# LEDS.net
KiCad netlist of a schematic drawn in EAGLE
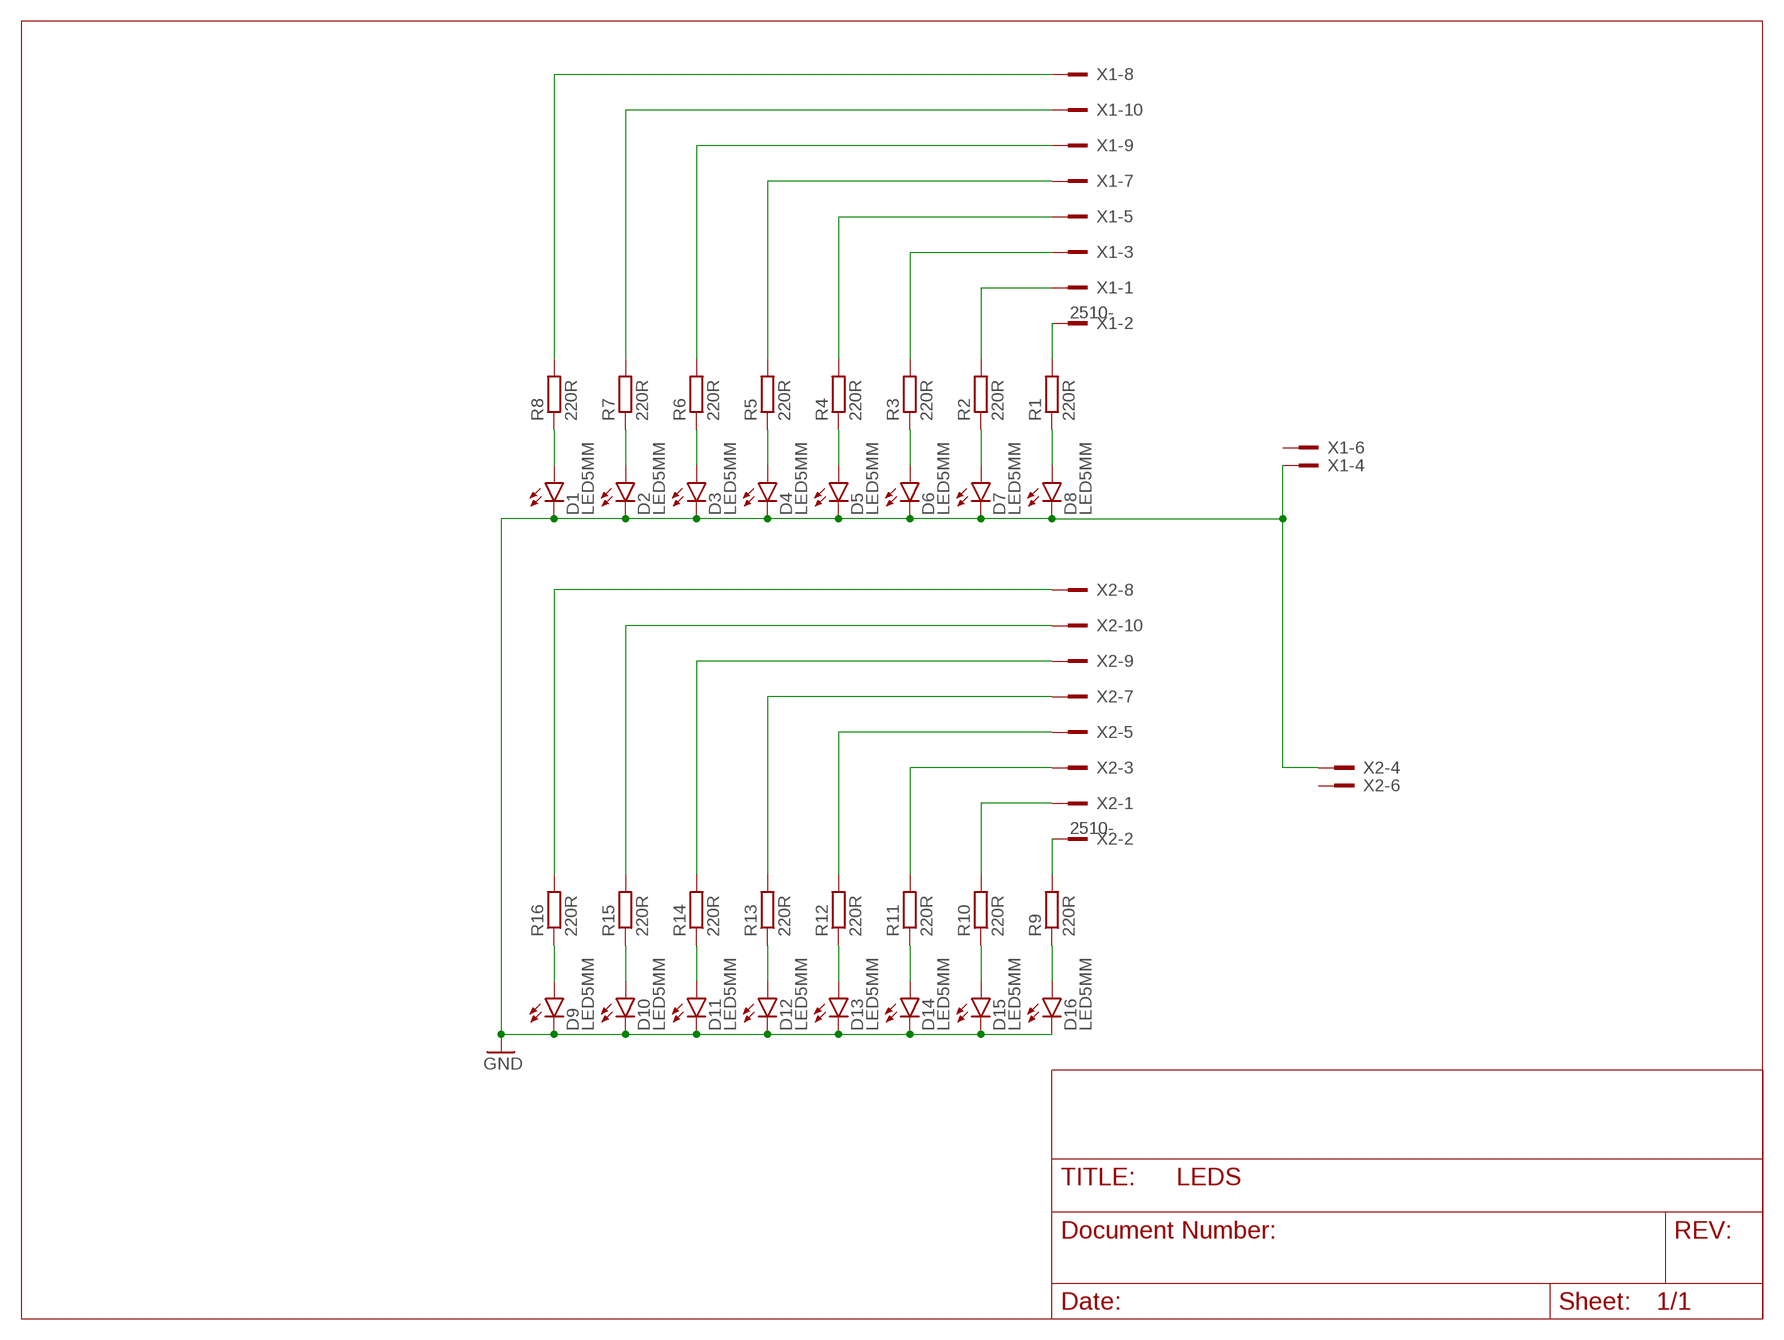
[diagram p0: schematic, sheet 1]

(export (version "E")
  (design (tool "Eeschema 10.0.6"))
  (components
    (comp (ref "D1")
      (value "LED5MM")
      (footprint "eagle-import:LED5MM")
      (libsource (lib "eagle-import") (part "LED5MM"))
    )
    (comp (ref "D2")
      (value "LED5MM")
      (footprint "eagle-import:LED5MM")
      (libsource (lib "eagle-import") (part "LED5MM"))
    )
    (comp (ref "D3")
      (value "LED5MM")
      (footprint "eagle-import:LED5MM")
      (libsource (lib "eagle-import") (part "LED5MM"))
    )
    (comp (ref "D4")
      (value "LED5MM")
      (footprint "eagle-import:LED5MM")
      (libsource (lib "eagle-import") (part "LED5MM"))
    )
    (comp (ref "D5")
      (value "LED5MM")
      (footprint "eagle-import:LED5MM")
      (libsource (lib "eagle-import") (part "LED5MM"))
    )
    (comp (ref "D6")
      (value "LED5MM")
      (footprint "eagle-import:LED5MM")
      (libsource (lib "eagle-import") (part "LED5MM"))
    )
    (comp (ref "D7")
      (value "LED5MM")
      (footprint "eagle-import:LED5MM")
      (libsource (lib "eagle-import") (part "LED5MM"))
    )
    (comp (ref "D8")
      (value "LED5MM")
      (footprint "eagle-import:LED5MM")
      (libsource (lib "eagle-import") (part "LED5MM"))
    )
    (comp (ref "D9")
      (value "LED5MM")
      (footprint "eagle-import:LED5MM")
      (libsource (lib "eagle-import") (part "LED5MM"))
    )
    (comp (ref "D10")
      (value "LED5MM")
      (footprint "eagle-import:LED5MM")
      (libsource (lib "eagle-import") (part "LED5MM"))
    )
    (comp (ref "D11")
      (value "LED5MM")
      (footprint "eagle-import:LED5MM")
      (libsource (lib "eagle-import") (part "LED5MM"))
    )
    (comp (ref "D12")
      (value "LED5MM")
      (footprint "eagle-import:LED5MM")
      (libsource (lib "eagle-import") (part "LED5MM"))
    )
    (comp (ref "D13")
      (value "LED5MM")
      (footprint "eagle-import:LED5MM")
      (libsource (lib "eagle-import") (part "LED5MM"))
    )
    (comp (ref "D14")
      (value "LED5MM")
      (footprint "eagle-import:LED5MM")
      (libsource (lib "eagle-import") (part "LED5MM"))
    )
    (comp (ref "D15")
      (value "LED5MM")
      (footprint "eagle-import:LED5MM")
      (libsource (lib "eagle-import") (part "LED5MM"))
    )
    (comp (ref "D16")
      (value "LED5MM")
      (footprint "eagle-import:LED5MM")
      (libsource (lib "eagle-import") (part "LED5MM"))
    )
    (comp (ref "R1")
      (value "220R")
      (footprint "eagle-import:0204_ELVYS")
      (libsource (lib "eagle-import") (part "R-EU_"))
    )
    (comp (ref "R2")
      (value "220R")
      (footprint "eagle-import:0204_ELVYS")
      (libsource (lib "eagle-import") (part "R-EU_"))
    )
    (comp (ref "R3")
      (value "220R")
      (footprint "eagle-import:0204_ELVYS")
      (libsource (lib "eagle-import") (part "R-EU_"))
    )
    (comp (ref "R4")
      (value "220R")
      (footprint "eagle-import:0204_ELVYS")
      (libsource (lib "eagle-import") (part "R-EU_"))
    )
    (comp (ref "R5")
      (value "220R")
      (footprint "eagle-import:0204_ELVYS")
      (libsource (lib "eagle-import") (part "R-EU_"))
    )
    (comp (ref "R6")
      (value "220R")
      (footprint "eagle-import:0204_ELVYS")
      (libsource (lib "eagle-import") (part "R-EU_"))
    )
    (comp (ref "R7")
      (value "220R")
      (footprint "eagle-import:0204_ELVYS")
      (libsource (lib "eagle-import") (part "R-EU_"))
    )
    (comp (ref "R8")
      (value "220R")
      (footprint "eagle-import:0204_ELVYS")
      (libsource (lib "eagle-import") (part "R-EU_"))
    )
    (comp (ref "R9")
      (value "220R")
      (footprint "eagle-import:0204_ELVYS")
      (libsource (lib "eagle-import") (part "R-EU_"))
    )
    (comp (ref "R10")
      (value "220R")
      (footprint "eagle-import:0204_ELVYS")
      (libsource (lib "eagle-import") (part "R-EU_"))
    )
    (comp (ref "R11")
      (value "220R")
      (footprint "eagle-import:0204_ELVYS")
      (libsource (lib "eagle-import") (part "R-EU_"))
    )
    (comp (ref "R12")
      (value "220R")
      (footprint "eagle-import:0204_ELVYS")
      (libsource (lib "eagle-import") (part "R-EU_"))
    )
    (comp (ref "R13")
      (value "220R")
      (footprint "eagle-import:0204_ELVYS")
      (libsource (lib "eagle-import") (part "R-EU_"))
    )
    (comp (ref "R14")
      (value "220R")
      (footprint "eagle-import:0204_ELVYS")
      (libsource (lib "eagle-import") (part "R-EU_"))
    )
    (comp (ref "R15")
      (value "220R")
      (footprint "eagle-import:0204_ELVYS")
      (libsource (lib "eagle-import") (part "R-EU_"))
    )
    (comp (ref "R16")
      (value "220R")
      (footprint "eagle-import:0204_ELVYS")
      (libsource (lib "eagle-import") (part "R-EU_"))
    )
    (comp (ref "X1")
      (value "2510-")
      (footprint "eagle-import:PAK100_2500-10")
      (fields (field (name "MF") "3M") (field (name "MPN") "2510-6002UB"))
      (libsource (lib "eagle-import") (part "2510-"))
    )
    (comp (ref "X2")
      (value "2510-")
      (footprint "eagle-import:PAK100_2500-10")
      (fields (field (name "MF") "3M") (field (name "MPN") "2510-6002UB"))
      (libsource (lib "eagle-import") (part "2510-"))
    )
  )
  (nets
    (net (code "1") (name "GND") (class "Default")
      (node (ref "D1") (pin "K") (pinfunction "C_K") (pintype "passive"))
      (node (ref "D10") (pin "K") (pinfunction "C_K") (pintype "passive"))
      (node (ref "D11") (pin "K") (pinfunction "C_K") (pintype "passive"))
      (node (ref "D12") (pin "K") (pinfunction "C_K") (pintype "passive"))
      (node (ref "D13") (pin "K") (pinfunction "C_K") (pintype "passive"))
      (node (ref "D14") (pin "K") (pinfunction "C_K") (pintype "passive"))
      (node (ref "D15") (pin "K") (pinfunction "C_K") (pintype "passive"))
      (node (ref "D16") (pin "K") (pinfunction "C_K") (pintype "passive"))
      (node (ref "D2") (pin "K") (pinfunction "C_K") (pintype "passive"))
      (node (ref "D3") (pin "K") (pinfunction "C_K") (pintype "passive"))
      (node (ref "D4") (pin "K") (pinfunction "C_K") (pintype "passive"))
      (node (ref "D5") (pin "K") (pinfunction "C_K") (pintype "passive"))
      (node (ref "D6") (pin "K") (pinfunction "C_K") (pintype "passive"))
      (node (ref "D7") (pin "K") (pinfunction "C_K") (pintype "passive"))
      (node (ref "D8") (pin "K") (pinfunction "C_K") (pintype "passive"))
      (node (ref "D9") (pin "K") (pinfunction "C_K") (pintype "passive"))
      (node (ref "X1") (pin "4") (pinfunction "KL_4") (pintype "passive"))
      (node (ref "X2") (pin "4") (pinfunction "KL_4") (pintype "passive"))
    )
    (net (code "2") (name "Net-(R1-1)") (class "Default")
      (node (ref "D8") (pin "A") (pinfunction "A_A") (pintype "passive"))
      (node (ref "R1") (pin "P$1") (pinfunction "1_P$1") (pintype "passive"))
    )
    (net (code "3") (name "Net-(R1-2)") (class "Default")
      (node (ref "R1") (pin "P$2") (pinfunction "2_P$2") (pintype "passive"))
      (node (ref "X1") (pin "2") (pinfunction "KL_2") (pintype "passive"))
    )
    (net (code "4") (name "Net-(R2-1)") (class "Default")
      (node (ref "D7") (pin "A") (pinfunction "A_A") (pintype "passive"))
      (node (ref "R2") (pin "P$1") (pinfunction "1_P$1") (pintype "passive"))
    )
    (net (code "5") (name "Net-(R2-2)") (class "Default")
      (node (ref "R2") (pin "P$2") (pinfunction "2_P$2") (pintype "passive"))
      (node (ref "X1") (pin "1") (pinfunction "KL_1") (pintype "passive"))
    )
    (net (code "6") (name "Net-(R3-1)") (class "Default")
      (node (ref "D6") (pin "A") (pinfunction "A_A") (pintype "passive"))
      (node (ref "R3") (pin "P$1") (pinfunction "1_P$1") (pintype "passive"))
    )
    (net (code "7") (name "Net-(R3-2)") (class "Default")
      (node (ref "R3") (pin "P$2") (pinfunction "2_P$2") (pintype "passive"))
      (node (ref "X1") (pin "3") (pinfunction "KL_3") (pintype "passive"))
    )
    (net (code "8") (name "Net-(R4-1)") (class "Default")
      (node (ref "D5") (pin "A") (pinfunction "A_A") (pintype "passive"))
      (node (ref "R4") (pin "P$1") (pinfunction "1_P$1") (pintype "passive"))
    )
    (net (code "9") (name "Net-(R4-2)") (class "Default")
      (node (ref "R4") (pin "P$2") (pinfunction "2_P$2") (pintype "passive"))
      (node (ref "X1") (pin "5") (pinfunction "KL_5") (pintype "passive"))
    )
    (net (code "10") (name "Net-(R5-1)") (class "Default")
      (node (ref "D4") (pin "A") (pinfunction "A_A") (pintype "passive"))
      (node (ref "R5") (pin "P$1") (pinfunction "1_P$1") (pintype "passive"))
    )
    (net (code "11") (name "Net-(R5-2)") (class "Default")
      (node (ref "R5") (pin "P$2") (pinfunction "2_P$2") (pintype "passive"))
      (node (ref "X1") (pin "7") (pinfunction "KL_7") (pintype "passive"))
    )
    (net (code "12") (name "Net-(R6-1)") (class "Default")
      (node (ref "D3") (pin "A") (pinfunction "A_A") (pintype "passive"))
      (node (ref "R6") (pin "P$1") (pinfunction "1_P$1") (pintype "passive"))
    )
    (net (code "13") (name "Net-(R6-2)") (class "Default")
      (node (ref "R6") (pin "P$2") (pinfunction "2_P$2") (pintype "passive"))
      (node (ref "X1") (pin "9") (pinfunction "KL_9") (pintype "passive"))
    )
    (net (code "14") (name "Net-(R7-1)") (class "Default")
      (node (ref "D2") (pin "A") (pinfunction "A_A") (pintype "passive"))
      (node (ref "R7") (pin "P$1") (pinfunction "1_P$1") (pintype "passive"))
    )
    (net (code "15") (name "Net-(R7-2)") (class "Default")
      (node (ref "R7") (pin "P$2") (pinfunction "2_P$2") (pintype "passive"))
      (node (ref "X1") (pin "10") (pinfunction "KL_10") (pintype "passive"))
    )
    (net (code "16") (name "Net-(R8-1)") (class "Default")
      (node (ref "D1") (pin "A") (pinfunction "A_A") (pintype "passive"))
      (node (ref "R8") (pin "P$1") (pinfunction "1_P$1") (pintype "passive"))
    )
    (net (code "17") (name "Net-(R8-2)") (class "Default")
      (node (ref "R8") (pin "P$2") (pinfunction "2_P$2") (pintype "passive"))
      (node (ref "X1") (pin "8") (pinfunction "KL_8") (pintype "passive"))
    )
    (net (code "18") (name "Net-(R9-1)") (class "Default")
      (node (ref "D16") (pin "A") (pinfunction "A_A") (pintype "passive"))
      (node (ref "R9") (pin "P$1") (pinfunction "1_P$1") (pintype "passive"))
    )
    (net (code "19") (name "Net-(R9-2)") (class "Default")
      (node (ref "R9") (pin "P$2") (pinfunction "2_P$2") (pintype "passive"))
      (node (ref "X2") (pin "2") (pinfunction "KL_2") (pintype "passive"))
    )
    (net (code "20") (name "Net-(R10-1)") (class "Default")
      (node (ref "D15") (pin "A") (pinfunction "A_A") (pintype "passive"))
      (node (ref "R10") (pin "P$1") (pinfunction "1_P$1") (pintype "passive"))
    )
    (net (code "21") (name "Net-(R10-2)") (class "Default")
      (node (ref "R10") (pin "P$2") (pinfunction "2_P$2") (pintype "passive"))
      (node (ref "X2") (pin "1") (pinfunction "KL_1") (pintype "passive"))
    )
    (net (code "22") (name "Net-(R11-1)") (class "Default")
      (node (ref "D14") (pin "A") (pinfunction "A_A") (pintype "passive"))
      (node (ref "R11") (pin "P$1") (pinfunction "1_P$1") (pintype "passive"))
    )
    (net (code "23") (name "Net-(R11-2)") (class "Default")
      (node (ref "R11") (pin "P$2") (pinfunction "2_P$2") (pintype "passive"))
      (node (ref "X2") (pin "3") (pinfunction "KL_3") (pintype "passive"))
    )
    (net (code "24") (name "Net-(R12-1)") (class "Default")
      (node (ref "D13") (pin "A") (pinfunction "A_A") (pintype "passive"))
      (node (ref "R12") (pin "P$1") (pinfunction "1_P$1") (pintype "passive"))
    )
    (net (code "25") (name "Net-(R12-2)") (class "Default")
      (node (ref "R12") (pin "P$2") (pinfunction "2_P$2") (pintype "passive"))
      (node (ref "X2") (pin "5") (pinfunction "KL_5") (pintype "passive"))
    )
    (net (code "26") (name "Net-(R13-1)") (class "Default")
      (node (ref "D12") (pin "A") (pinfunction "A_A") (pintype "passive"))
      (node (ref "R13") (pin "P$1") (pinfunction "1_P$1") (pintype "passive"))
    )
    (net (code "27") (name "Net-(R13-2)") (class "Default")
      (node (ref "R13") (pin "P$2") (pinfunction "2_P$2") (pintype "passive"))
      (node (ref "X2") (pin "7") (pinfunction "KL_7") (pintype "passive"))
    )
    (net (code "28") (name "Net-(R14-1)") (class "Default")
      (node (ref "D11") (pin "A") (pinfunction "A_A") (pintype "passive"))
      (node (ref "R14") (pin "P$1") (pinfunction "1_P$1") (pintype "passive"))
    )
    (net (code "29") (name "Net-(R14-2)") (class "Default")
      (node (ref "R14") (pin "P$2") (pinfunction "2_P$2") (pintype "passive"))
      (node (ref "X2") (pin "9") (pinfunction "KL_9") (pintype "passive"))
    )
    (net (code "30") (name "Net-(R15-1)") (class "Default")
      (node (ref "D10") (pin "A") (pinfunction "A_A") (pintype "passive"))
      (node (ref "R15") (pin "P$1") (pinfunction "1_P$1") (pintype "passive"))
    )
    (net (code "31") (name "Net-(R15-2)") (class "Default")
      (node (ref "R15") (pin "P$2") (pinfunction "2_P$2") (pintype "passive"))
      (node (ref "X2") (pin "10") (pinfunction "KL_10") (pintype "passive"))
    )
    (net (code "32") (name "Net-(R16-1)") (class "Default")
      (node (ref "D9") (pin "A") (pinfunction "A_A") (pintype "passive"))
      (node (ref "R16") (pin "P$1") (pinfunction "1_P$1") (pintype "passive"))
    )
    (net (code "33") (name "Net-(R16-2)") (class "Default")
      (node (ref "R16") (pin "P$2") (pinfunction "2_P$2") (pintype "passive"))
      (node (ref "X2") (pin "8") (pinfunction "KL_8") (pintype "passive"))
    )
    (net (code "34") (name "unconnected-(X1G-KL-Pad6)") (class "Default")
      (node (ref "X1") (pin "6") (pinfunction "KL_6") (pintype "passive"))
    )
    (net (code "35") (name "unconnected-(X2G-KL-Pad6)") (class "Default")
      (node (ref "X2") (pin "6") (pinfunction "KL_6") (pintype "passive"))
    )
  )
)
